# Servo.net
KiCad netlist of a schematic drawn in Altium Designer
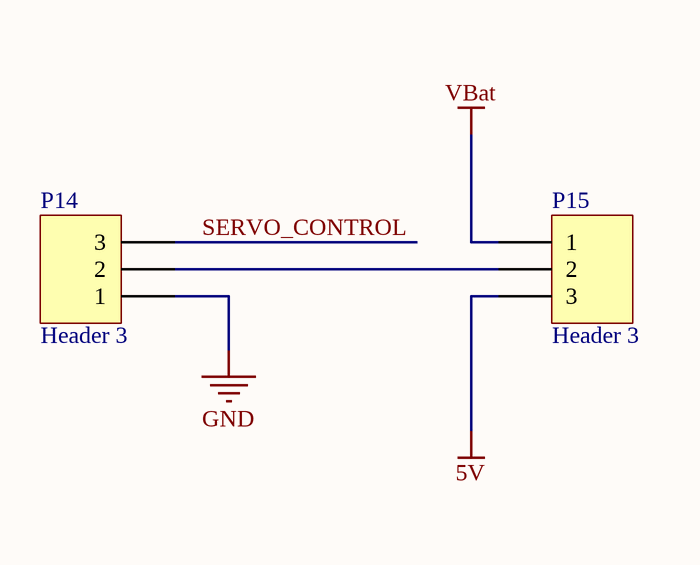
[diagram p0: Servo.SchDoc]

(export (version "E")
  (design (tool "Eeschema 10.0.6"))
  (components
    (comp (ref "P14")
      (value "Header 3")
      (footprint "HDR1X3")
      (description "Header, 3-Pin")
      (fields (field (name "PUBLISHER") "Altium Limited"))
      (libsource (lib "Miscellaneous Connectors") (part "Header 3"))
    )
    (comp (ref "P15")
      (value "Header 3")
      (footprint "HDR1X3")
      (description "Header, 3-Pin")
      (fields (field (name "PUBLISHER") "Altium Limited"))
      (libsource (lib "") (part "Header 3_1"))
    )
  )
  (nets
    (net (code "1") (name "/SERVO_CONTROL") (class "Default")
      (node (ref "P14") (pin "3") (pinfunction "3_3") (pintype "passive"))
    )
    (net (code "2") (name "5V") (class "Default")
      (node (ref "P15") (pin "3") (pinfunction "3_3") (pintype "passive"))
    )
    (net (code "3") (name "GND") (class "Default")
      (node (ref "P14") (pin "1") (pinfunction "1_1") (pintype "passive"))
    )
    (net (code "4") (name "Net-(P14-Pad2)") (class "Default")
      (node (ref "P14") (pin "2") (pinfunction "2_2") (pintype "passive"))
      (node (ref "P15") (pin "2") (pinfunction "2_2") (pintype "passive"))
    )
    (net (code "5") (name "VBat") (class "Default")
      (node (ref "P15") (pin "1") (pinfunction "1_1") (pintype "passive"))
    )
  )
)
